# MosFetsDrive_2_1.net
KiCad netlist of a schematic drawn in Altium Designer
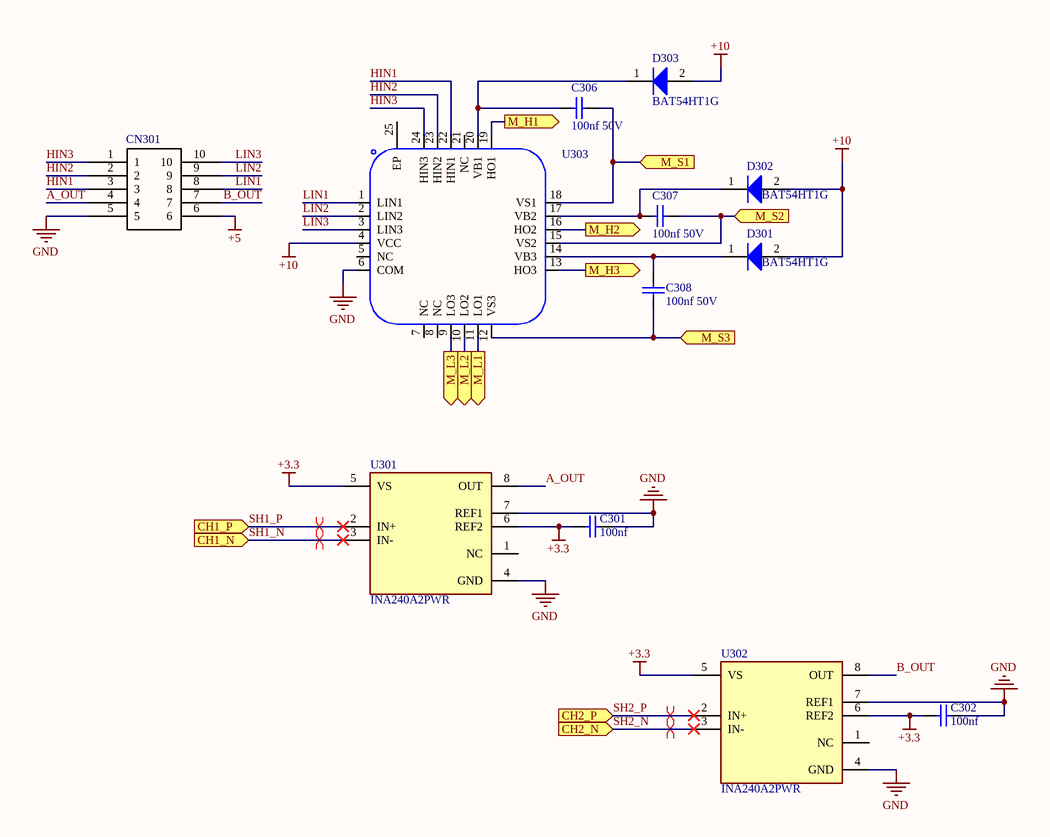
[diagram p0: MosFetsDrive_2_1.SchDoc]

(export (version "E")
  (design (tool "Eeschema 10.0.6"))
  (components
    (comp (ref "C301")
      (value "100nf")
      (footprint "CAPC1608X90X35ML10T15")
      (description "Chip Capacitor, 10 nF, +/- 10%, 50 V, -55 to 125 degC, 0603 (1608 Metric), RoHS, Tape and Reel")
      (fields (field (name "VOLTAGE") "50V") (field (name "TOLERANCE") "10%"))
      (libsource (lib "Altium Content Vault") (part "CAP-NP-2"))
    )
    (comp (ref "C302")
      (value "100nf")
      (footprint "CAPC1608X90X35ML10T15")
      (description "Chip Capacitor, 10 nF, +/- 10%, 50 V, -55 to 125 degC, 0603 (1608 Metric), RoHS, Tape and Reel")
      (fields (field (name "VOLTAGE") "50V") (field (name "TOLERANCE") "10%"))
      (libsource (lib "Altium Content Vault") (part "CAP-NP-2"))
    )
    (comp (ref "C306")
      (value "100nf 50V")
      (footprint "CAPC1005X60X30ML05T10")
      (fields (field (name "MANUFACTURER") "Kemet") (field (name "PART NUMBER") "C0402C104K8PACTU"))
      (libsource (lib "Altium Content Vault") (part "CAP"))
    )
    (comp (ref "C307")
      (value "100nf 50V")
      (footprint "CAPC1005X60X30ML05T10")
      (fields (field (name "MANUFACTURER") "Kemet") (field (name "PART NUMBER") "C0402C104K8PACTU"))
      (libsource (lib "Altium Content Vault") (part "CAP"))
    )
    (comp (ref "C308")
      (value "100nf 50V")
      (footprint "CAPC1005X60X30ML05T10")
      (fields (field (name "MANUFACTURER") "Kemet") (field (name "PART NUMBER") "C0402C104K8PACTU"))
      (libsource (lib "Altium Content Vault") (part "CAP"))
    )
    (comp (ref "CN301") (value "~") (footprint "2X10Pin") (libsource (lib "10P") (part "Component_1")))
    (comp (ref "D301")
      (value "BAT54HT1G")
      (footprint "ONSC-SOD-323-2-477-02_V")
      (description "Schottky Barrier Diode, 2-Pin SOD-323, Pb-Free, Tape and Reel")
      (fields (field (name "MANUFACTURER") "On Semiconductor"))
      (libsource (lib "Altium Content Vault") (part "ONSC-D-K1A2-2"))
    )
    (comp (ref "D302")
      (value "BAT54HT1G")
      (footprint "ONSC-SOD-323-2-477-02_V")
      (description "Schottky Barrier Diode, 2-Pin SOD-323, Pb-Free, Tape and Reel")
      (fields (field (name "MANUFACTURER") "On Semiconductor"))
      (libsource (lib "Altium Content Vault") (part "ONSC-D-K1A2-2"))
    )
    (comp (ref "D303")
      (value "BAT54HT1G")
      (footprint "ONSC-SOD-323-2-477-02_V")
      (description "Schottky Barrier Diode, 2-Pin SOD-323, Pb-Free, Tape and Reel")
      (fields (field (name "MANUFACTURER") "On Semiconductor"))
      (libsource (lib "Altium Content Vault") (part "ONSC-D-K1A2-2"))
    )
    (comp (ref "U301")
      (value "INA240A2PWR")
      (footprint "FP-PW0008A-MFG")
      (description "IC AMP CURRENT SENSE 8-TSSOP")
      (fields
        (field (name "OCTOPART") "https://octopart.com/ina240a2pwr-texas+instruments-75431049")
        (field (name "MANUFACTURER") "Texas Instruments")
      )
      (libsource (lib "Altium Content Vault") (part "98c6b1d0971071ba4d7dac1d4a4ea92"))
    )
    (comp (ref "U302")
      (value "INA240A2PWR")
      (footprint "FP-PW0008A-MFG")
      (description "IC AMP CURRENT SENSE 8-TSSOP")
      (fields
        (field (name "OCTOPART") "https://octopart.com/ina240a2pwr-texas+instruments-75431049")
        (field (name "MANUFACTURER") "Texas Instruments")
      )
      (libsource (lib "Altium Content Vault") (part "98c6b1d0971071ba4d7dac1d4a4ea92"))
    )
    (comp (ref "U303")
      (value "FD6288Q")
      (footprint "QFN-24_L4.0-W4.0-P0.50-BL-EP2.6")
      (fields (field (name "MANUFACTURER") "Fortior Tech(峰岹)"))
      (libsource (lib "FD6288Q") (part "FD6288Q"))
    )
  )
  (nets
    (net (code "1") (name "+3.3") (class "Default")
      (node (ref "C301") (pin "2") (pinfunction "2_2") (pintype "passive"))
      (node (ref "C302") (pin "2") (pinfunction "2_2") (pintype "passive"))
      (node (ref "U301") (pin "5") (pinfunction "VS_5") (pintype "power_in"))
      (node (ref "U301") (pin "6") (pinfunction "REF2_6") (pintype "passive"))
      (node (ref "U302") (pin "5") (pinfunction "VS_5") (pintype "power_in"))
      (node (ref "U302") (pin "6") (pinfunction "REF2_6") (pintype "passive"))
    )
    (net (code "2") (name "+5") (class "Default")
      (node (ref "CN301") (pin "6") (pinfunction "6_6") (pintype "passive"))
    )
    (net (code "3") (name "+10") (class "Default")
      (node (ref "D301") (pin "2") (pinfunction "A_2") (pintype "passive"))
      (node (ref "D302") (pin "2") (pinfunction "A_2") (pintype "passive"))
      (node (ref "D303") (pin "2") (pinfunction "A_2") (pintype "passive"))
      (node (ref "U303") (pin "4") (pinfunction "VCC_4") (pintype "passive"))
    )
    (net (code "4") (name "/A_OUT") (class "Default")
      (node (ref "CN301") (pin "4") (pinfunction "4_4") (pintype "passive"))
      (node (ref "U301") (pin "8") (pinfunction "OUT_8") (pintype "passive"))
    )
    (net (code "5") (name "/B_OUT") (class "Default")
      (node (ref "CN301") (pin "7") (pinfunction "7_7") (pintype "passive"))
      (node (ref "U302") (pin "8") (pinfunction "OUT_8") (pintype "passive"))
    )
    (net (code "6") (name "/HIN1") (class "Default")
      (node (ref "CN301") (pin "3") (pinfunction "3_3") (pintype "passive"))
      (node (ref "U303") (pin "22") (pinfunction "HIN1_22") (pintype "passive"))
    )
    (net (code "7") (name "/HIN2") (class "Default")
      (node (ref "CN301") (pin "2") (pinfunction "2_2") (pintype "passive"))
      (node (ref "U303") (pin "23") (pinfunction "HIN2_23") (pintype "passive"))
    )
    (net (code "8") (name "/HIN3") (class "Default")
      (node (ref "CN301") (pin "1") (pinfunction "1_1") (pintype "passive"))
      (node (ref "U303") (pin "24") (pinfunction "HIN3_24") (pintype "passive"))
    )
    (net (code "9") (name "/LIN1") (class "Default")
      (node (ref "CN301") (pin "8") (pinfunction "8_8") (pintype "passive"))
      (node (ref "U303") (pin "1") (pinfunction "LIN1_1") (pintype "passive"))
    )
    (net (code "10") (name "/LIN2") (class "Default")
      (node (ref "CN301") (pin "9") (pinfunction "9_9") (pintype "passive"))
      (node (ref "U303") (pin "2") (pinfunction "LIN2_2") (pintype "passive"))
    )
    (net (code "11") (name "/LIN3") (class "Default")
      (node (ref "CN301") (pin "10") (pinfunction "10_10") (pintype "passive"))
      (node (ref "U303") (pin "3") (pinfunction "LIN3_3") (pintype "passive"))
    )
    (net (code "12") (name "/M_H1") (class "Default")
      (node (ref "U303") (pin "19") (pinfunction "HO1_19") (pintype "passive"))
    )
    (net (code "13") (name "/M_H2") (class "Default")
      (node (ref "U303") (pin "16") (pinfunction "HO2_16") (pintype "passive"))
    )
    (net (code "14") (name "/M_H3") (class "Default")
      (node (ref "U303") (pin "13") (pinfunction "HO3_13") (pintype "passive"))
    )
    (net (code "15") (name "/M_L1") (class "Default")
      (node (ref "U303") (pin "11") (pinfunction "LO1_11") (pintype "passive"))
    )
    (net (code "16") (name "/M_L2") (class "Default")
      (node (ref "U303") (pin "10") (pinfunction "LO2_10") (pintype "passive"))
    )
    (net (code "17") (name "/M_L3") (class "Default")
      (node (ref "U303") (pin "9") (pinfunction "LO3_9") (pintype "passive"))
    )
    (net (code "18") (name "/M_S1") (class "Default")
      (node (ref "C306") (pin "2") (pinfunction "2_2") (pintype "passive"))
      (node (ref "U303") (pin "18") (pinfunction "VS1_18") (pintype "passive"))
    )
    (net (code "19") (name "/M_S2") (class "Default")
      (node (ref "C307") (pin "2") (pinfunction "2_2") (pintype "passive"))
      (node (ref "U303") (pin "15") (pinfunction "VS2_15") (pintype "passive"))
    )
    (net (code "20") (name "/M_S3") (class "Default")
      (node (ref "C308") (pin "1") (pinfunction "1_1") (pintype "passive"))
      (node (ref "U303") (pin "12") (pinfunction "VS3_12") (pintype "passive"))
    )
    (net (code "21") (name "/SH1_N") (class "Default")
      (node (ref "U301") (pin "3") (pinfunction "IN-_3") (pintype "tri_state+no_connect"))
    )
    (net (code "22") (name "/SH1_P") (class "Default")
      (node (ref "U301") (pin "2") (pinfunction "IN+_2") (pintype "tri_state+no_connect"))
    )
    (net (code "23") (name "/SH2_N") (class "Default")
      (node (ref "U302") (pin "3") (pinfunction "IN-_3") (pintype "tri_state+no_connect"))
    )
    (net (code "24") (name "/SH2_P") (class "Default")
      (node (ref "U302") (pin "2") (pinfunction "IN+_2") (pintype "tri_state+no_connect"))
    )
    (net (code "25") (name "GND") (class "Default")
      (node (ref "C301") (pin "1") (pinfunction "1_1") (pintype "passive"))
      (node (ref "C302") (pin "1") (pinfunction "1_1") (pintype "passive"))
      (node (ref "CN301") (pin "5") (pinfunction "5_5") (pintype "passive"))
      (node (ref "U301") (pin "4") (pinfunction "GND_4") (pintype "power_in"))
      (node (ref "U301") (pin "7") (pinfunction "REF1_7") (pintype "passive"))
      (node (ref "U302") (pin "4") (pinfunction "GND_4") (pintype "power_in"))
      (node (ref "U302") (pin "7") (pinfunction "REF1_7") (pintype "passive"))
      (node (ref "U303") (pin "6") (pinfunction "COM_6") (pintype "passive"))
    )
    (net (code "26") (name "Net-(D301-K)") (class "Default")
      (node (ref "C308") (pin "2") (pinfunction "2_2") (pintype "passive"))
      (node (ref "D301") (pin "1") (pinfunction "K_1") (pintype "passive"))
      (node (ref "U303") (pin "14") (pinfunction "VB3_14") (pintype "passive"))
    )
    (net (code "27") (name "Net-(D302-K)") (class "Default")
      (node (ref "C307") (pin "1") (pinfunction "1_1") (pintype "passive"))
      (node (ref "D302") (pin "1") (pinfunction "K_1") (pintype "passive"))
      (node (ref "U303") (pin "17") (pinfunction "VB2_17") (pintype "passive"))
    )
    (net (code "28") (name "Net-(D303-K)") (class "Default")
      (node (ref "C306") (pin "1") (pinfunction "1_1") (pintype "passive"))
      (node (ref "D303") (pin "1") (pinfunction "K_1") (pintype "passive"))
      (node (ref "U303") (pin "20") (pinfunction "VB1_20") (pintype "passive"))
    )
    (net (code "29") (name "unconnected-(U301-NC-Pad1)") (class "Default")
      (node (ref "U301") (pin "1") (pinfunction "NC_1") (pintype "passive"))
    )
    (net (code "30") (name "unconnected-(U302-NC-Pad1)") (class "Default")
      (node (ref "U302") (pin "1") (pinfunction "NC_1") (pintype "passive"))
    )
    (net (code "31") (name "unconnected-(U303-EP-Pad25)") (class "Default")
      (node (ref "U303") (pin "25") (pinfunction "EP_25") (pintype "passive"))
    )
    (net (code "32") (name "unconnected-(U303-NC-Pad5)") (class "Default")
      (node (ref "U303") (pin "5") (pinfunction "NC_5") (pintype "passive"))
    )
    (net (code "33") (name "unconnected-(U303-NC-Pad7)") (class "Default")
      (node (ref "U303") (pin "7") (pinfunction "NC_7") (pintype "passive"))
    )
    (net (code "34") (name "unconnected-(U303-NC-Pad8)") (class "Default")
      (node (ref "U303") (pin "8") (pinfunction "NC_8") (pintype "passive"))
    )
    (net (code "35") (name "unconnected-(U303-NC-Pad21)") (class "Default")
      (node (ref "U303") (pin "21") (pinfunction "NC_21") (pintype "passive"))
    )
  )
)
